# safebox.net
KiCad netlist of a schematic drawn in EAGLE
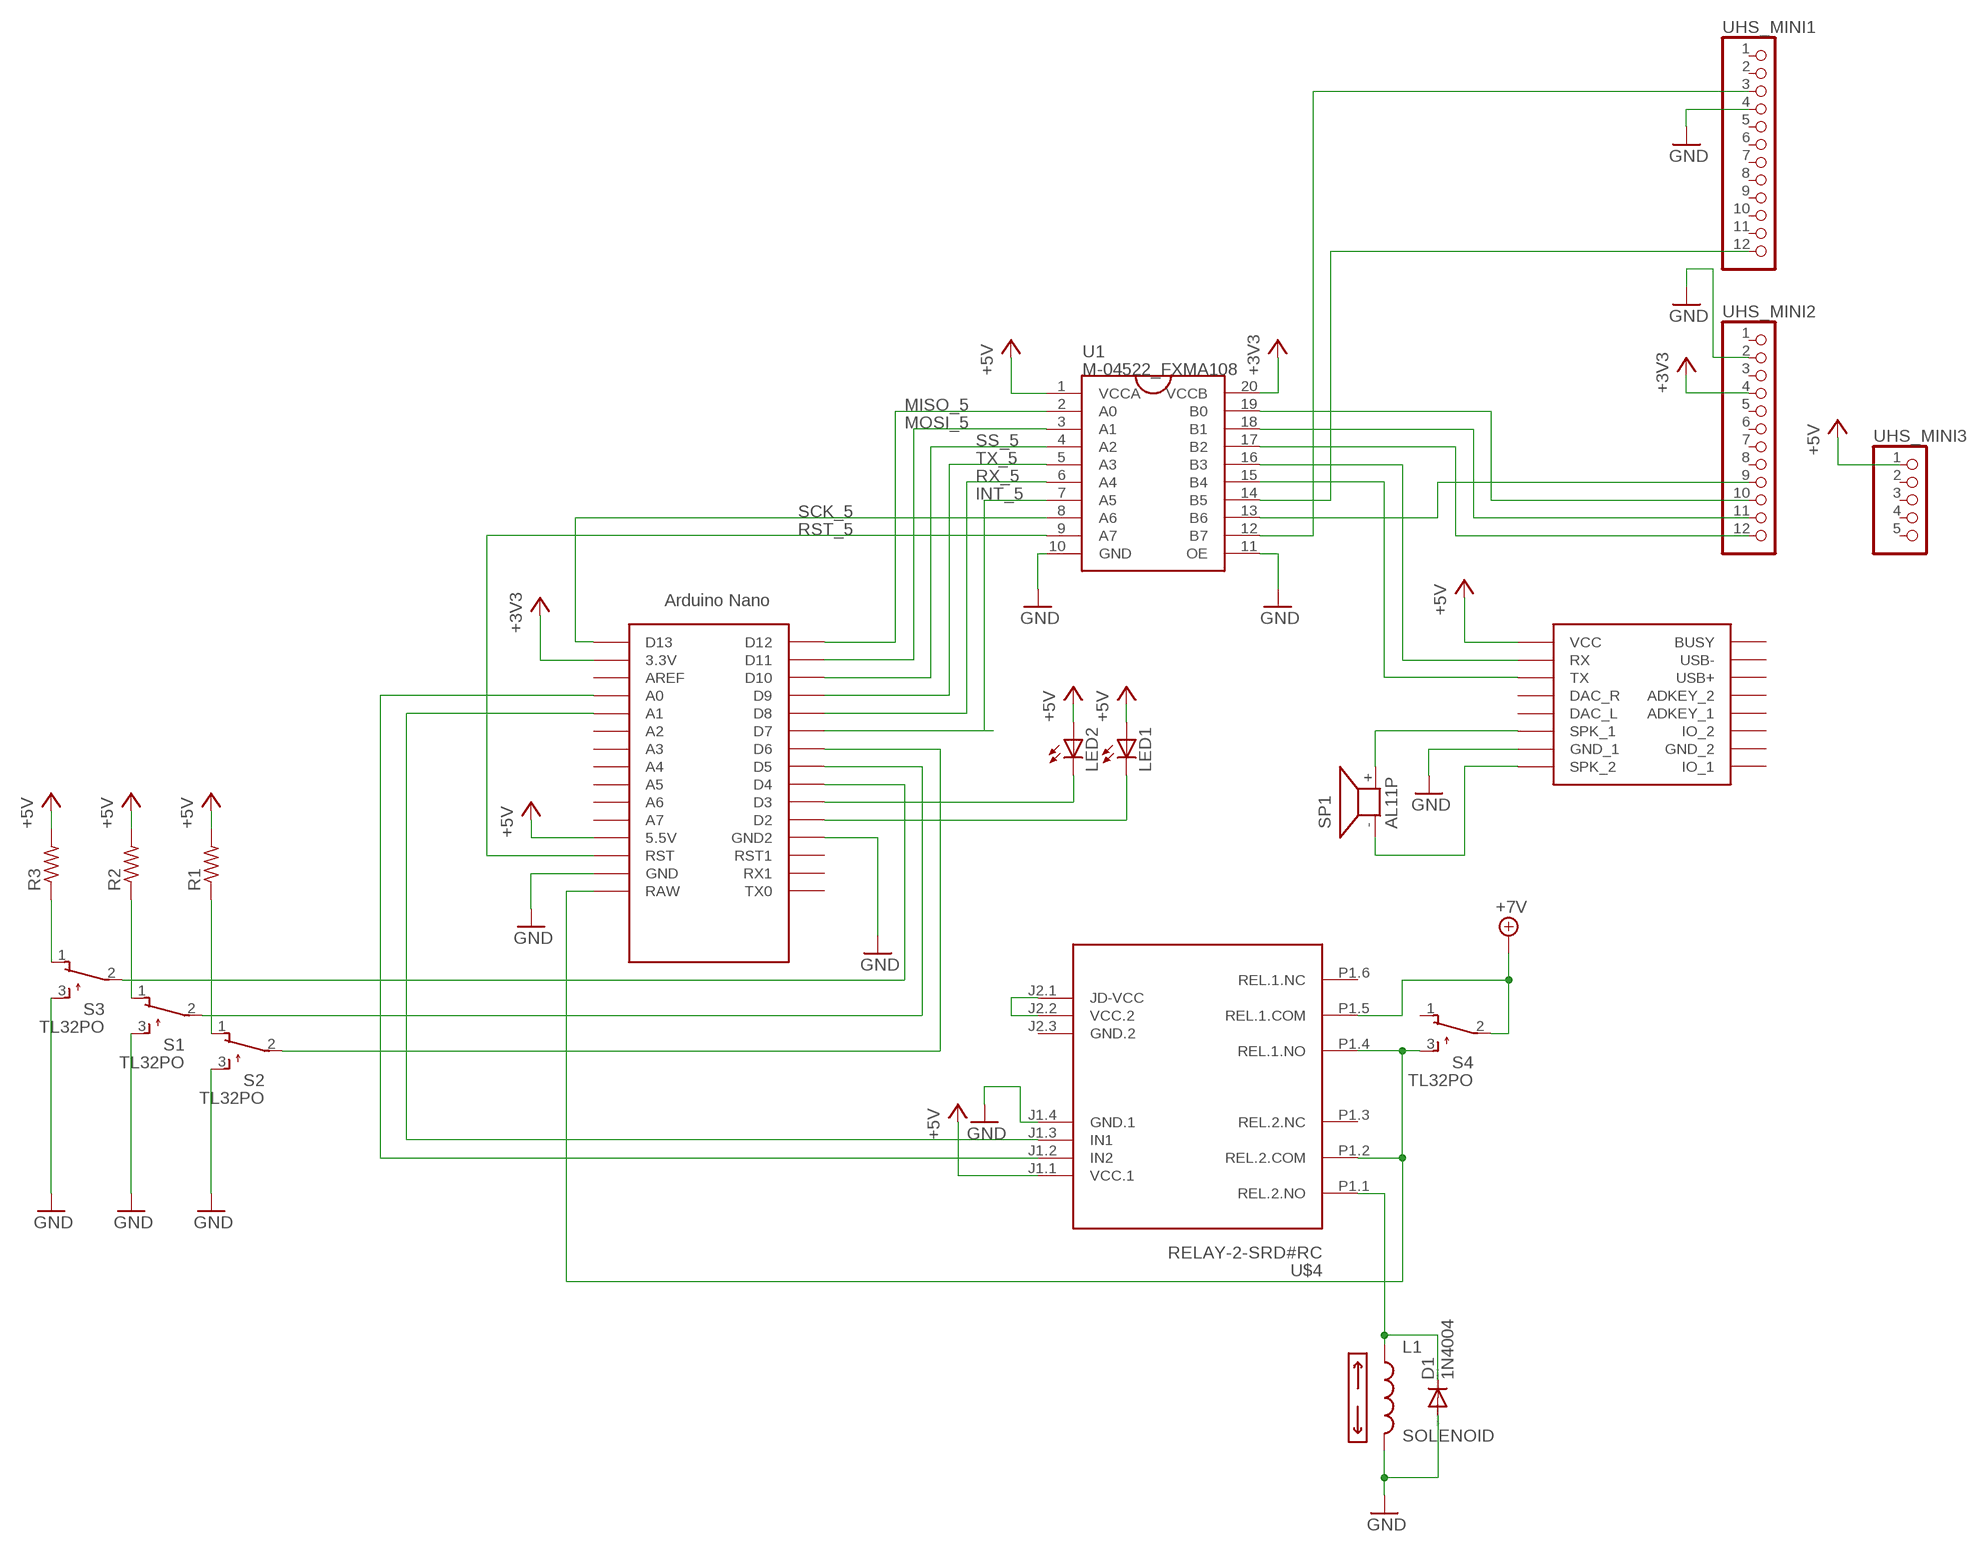
[diagram p0: schematic, sheet 1]

(export (version "E")
  (design (tool "Eeschema 10.0.6"))
  (components
    (comp (ref "D1")
      (value "1N4004")
      (footprint "eagle-import:DO41-10")
      (libsource (lib "eagle-import") (part "1N4004"))
    )
    (comp (ref "L1")
      (value "SOLENOID")
      (footprint "eagle-import:1X02")
      (libsource (lib "eagle-import") (part "SOLENOID"))
    )
    (comp (ref "LED1")
      (value "LED10MM")
      (footprint "eagle-import:LED10MM")
      (libsource (lib "eagle-import") (part "LED10MM"))
    )
    (comp (ref "LED2")
      (value "LED10MM")
      (footprint "eagle-import:LED10MM")
      (libsource (lib "eagle-import") (part "LED10MM"))
    )
    (comp (ref "R1")
      (value "R-US_0207/12")
      (footprint "eagle-import:0207_12")
      (libsource (lib "eagle-import") (part "R-US_0207/12"))
    )
    (comp (ref "R2")
      (value "R-US_0207/12")
      (footprint "eagle-import:0207_12")
      (libsource (lib "eagle-import") (part "R-US_0207/12"))
    )
    (comp (ref "R3")
      (value "R-US_0207/12")
      (footprint "eagle-import:0207_12")
      (libsource (lib "eagle-import") (part "R-US_0207/12"))
    )
    (comp (ref "S1")
      (value "TL32PO")
      (footprint "eagle-import:TL3XPO")
      (libsource (lib "eagle-import") (part "TL32PO"))
    )
    (comp (ref "S2")
      (value "TL32PO")
      (footprint "eagle-import:TL3XPO")
      (libsource (lib "eagle-import") (part "TL32PO"))
    )
    (comp (ref "S3")
      (value "TL32PO")
      (footprint "eagle-import:TL3XPO")
      (libsource (lib "eagle-import") (part "TL32PO"))
    )
    (comp (ref "S4")
      (value "TL32PO")
      (footprint "eagle-import:TL3XPO")
      (libsource (lib "eagle-import") (part "TL32PO"))
    )
    (comp (ref "SP1")
      (value "AL11P")
      (footprint "eagle-import:AL11P")
      (libsource (lib "eagle-import") (part "AL11P"))
    )
    (comp (ref "U$1")
      (value "NANO")
      (footprint "eagle-import:NANO")
      (libsource (lib "eagle-import") (part "NANO"))
    )
    (comp (ref "U$2")
      (value "DFPLAYER")
      (footprint "eagle-import:DFPLAYER")
      (libsource (lib "eagle-import") (part "DFPLAYER"))
    )
    (comp (ref "U$4")
      (value "RELAY-2-SRD#RC")
      (footprint "eagle-import:RELAY-2-SRD#RC")
      (libsource (lib "eagle-import") (part "RELAY-2-SRD#RC"))
    )
    (comp (ref "U1")
      (value "M-04522_FXMA108")
      (footprint "eagle-import:FXMA108")
      (libsource (lib "eagle-import") (part "M-04522_FXMA108"))
    )
    (comp (ref "UHS_MINI1")
      (value "PINHD-1X12")
      (footprint "eagle-import:1X12")
      (libsource (lib "eagle-import") (part "PINHD-1X12"))
    )
    (comp (ref "UHS_MINI2")
      (value "PINHD-1X12")
      (footprint "eagle-import:1X12")
      (libsource (lib "eagle-import") (part "PINHD-1X12"))
    )
    (comp (ref "UHS_MINI3")
      (value "PINHD-1X5")
      (footprint "eagle-import:1X05")
      (libsource (lib "eagle-import") (part "PINHD-1X5"))
    )
  )
  (nets
    (net (code "1") (name "+3V3") (class "Default")
      (node (ref "U$1") (pin "3.3V") (pinfunction "3.3V_3.3V") (pintype "bidirectional"))
      (node (ref "U1") (pin "20") (pinfunction "VCCB_20") (pintype "bidirectional"))
      (node (ref "UHS_MINI2") (pin "4") (pinfunction "4_4") (pintype "passive"))
    )
    (net (code "2") (name "+5V") (class "Default")
      (node (ref "LED1") (pin "A") (pinfunction "A_A") (pintype "passive"))
      (node (ref "LED2") (pin "A") (pinfunction "A_A") (pintype "passive"))
      (node (ref "R1") (pin "2") (pinfunction "2_2") (pintype "passive"))
      (node (ref "R2") (pin "2") (pinfunction "2_2") (pintype "passive"))
      (node (ref "R3") (pin "2") (pinfunction "2_2") (pintype "passive"))
      (node (ref "U$1") (pin "5V") (pinfunction "5.5V_5V") (pintype "bidirectional"))
      (node (ref "U$2") (pin "VCC") (pinfunction "VCC_VCC") (pintype "bidirectional"))
      (node (ref "U$4") (pin "J1.1") (pinfunction "VCC.1_J1.1") (pintype "power_in"))
      (node (ref "U1") (pin "1") (pinfunction "VCCA_1") (pintype "bidirectional"))
      (node (ref "UHS_MINI3") (pin "1") (pinfunction "1_1") (pintype "passive"))
    )
    (net (code "3") (name "+7V") (class "Default")
      (node (ref "S4") (pin "2") (pinfunction "P_2") (pintype "passive"))
      (node (ref "U$4") (pin "P1.5") (pinfunction "REL.1.COM_P1.5") (pintype "bidirectional"))
    )
    (net (code "4") (name "/GND.2") (class "Default")
      (node (ref "U$4") (pin "J2.3") (pinfunction "GND.2_J2.3") (pintype "power_in"))
    )
    (net (code "5") (name "/INT_5") (class "Default")
      (node (ref "U1") (pin "7") (pinfunction "A5_7") (pintype "bidirectional"))
    )
    (net (code "6") (name "/MISO_5") (class "Default")
      (node (ref "U$1") (pin "D12") (pinfunction "D12_D12") (pintype "bidirectional"))
      (node (ref "U1") (pin "2") (pinfunction "A0_2") (pintype "bidirectional"))
    )
    (net (code "7") (name "/MOSI_5") (class "Default")
      (node (ref "U$1") (pin "D11") (pinfunction "D11_D11") (pintype "bidirectional"))
      (node (ref "U1") (pin "3") (pinfunction "A1_3") (pintype "bidirectional"))
    )
    (net (code "8") (name "/RST_5") (class "Default")
      (node (ref "U$1") (pin "RST") (pinfunction "RST_RST") (pintype "bidirectional"))
      (node (ref "U1") (pin "9") (pinfunction "A7_9") (pintype "bidirectional"))
    )
    (net (code "9") (name "/RX_5") (class "Default")
      (node (ref "U$1") (pin "D8") (pinfunction "D8_D8") (pintype "bidirectional"))
      (node (ref "U1") (pin "6") (pinfunction "A4_6") (pintype "bidirectional"))
    )
    (net (code "10") (name "/SCK_5") (class "Default")
      (node (ref "U$1") (pin "D13") (pinfunction "D13_D13") (pintype "bidirectional"))
      (node (ref "U1") (pin "8") (pinfunction "A6_8") (pintype "bidirectional"))
    )
    (net (code "11") (name "/SS_5") (class "Default")
      (node (ref "U$1") (pin "D10") (pinfunction "D10_D10") (pintype "bidirectional"))
      (node (ref "U1") (pin "4") (pinfunction "A2_4") (pintype "bidirectional"))
    )
    (net (code "12") (name "/TX_5") (class "Default")
      (node (ref "U$1") (pin "D9") (pinfunction "D9_D9") (pintype "bidirectional"))
      (node (ref "U1") (pin "5") (pinfunction "A3_5") (pintype "bidirectional"))
    )
    (net (code "13") (name "GND") (class "Default")
      (node (ref "D1") (pin "A") (pinfunction "A_A") (pintype "passive"))
      (node (ref "L1") (pin "2") (pinfunction "2_2") (pintype "passive"))
      (node (ref "S1") (pin "3") (pinfunction "S_3") (pintype "passive"))
      (node (ref "S2") (pin "3") (pinfunction "S_3") (pintype "passive"))
      (node (ref "S3") (pin "3") (pinfunction "S_3") (pintype "passive"))
      (node (ref "U$1") (pin "GND") (pinfunction "GND_GND") (pintype "bidirectional"))
      (node (ref "U$1") (pin "GND1") (pinfunction "GND2_GND1") (pintype "bidirectional"))
      (node (ref "U$2") (pin "GND_1") (pinfunction "GND_1_GND_1") (pintype "bidirectional"))
      (node (ref "U$4") (pin "J1.4") (pinfunction "GND.1_J1.4") (pintype "power_in"))
      (node (ref "U1") (pin "10") (pinfunction "GND_10") (pintype "bidirectional"))
      (node (ref "U1") (pin "11") (pinfunction "OE_11") (pintype "bidirectional"))
      (node (ref "UHS_MINI1") (pin "4") (pinfunction "4_4") (pintype "passive"))
      (node (ref "UHS_MINI2") (pin "2") (pinfunction "2_2") (pintype "passive"))
    )
    (net (code "14") (name "Net-(LED1-C)") (class "Default")
      (node (ref "LED1") (pin "K") (pinfunction "C_K") (pintype "passive"))
      (node (ref "U$1") (pin "D2") (pinfunction "D2_D2") (pintype "bidirectional"))
    )
    (net (code "15") (name "Net-(LED2-C)") (class "Default")
      (node (ref "LED2") (pin "K") (pinfunction "C_K") (pintype "passive"))
      (node (ref "U$1") (pin "D3") (pinfunction "D3_D3") (pintype "bidirectional"))
    )
    (net (code "16") (name "Net-(S1-O)") (class "Default")
      (node (ref "R2") (pin "1") (pinfunction "1_1") (pintype "passive"))
      (node (ref "S1") (pin "1") (pinfunction "O_1") (pintype "passive"))
    )
    (net (code "17") (name "Net-(S1-P)") (class "Default")
      (node (ref "S1") (pin "2") (pinfunction "P_2") (pintype "passive"))
      (node (ref "U$1") (pin "D5") (pinfunction "D5_D5") (pintype "bidirectional"))
    )
    (net (code "18") (name "Net-(S2-O)") (class "Default")
      (node (ref "R1") (pin "1") (pinfunction "1_1") (pintype "passive"))
      (node (ref "S2") (pin "1") (pinfunction "O_1") (pintype "passive"))
    )
    (net (code "19") (name "Net-(S2-P)") (class "Default")
      (node (ref "S2") (pin "2") (pinfunction "P_2") (pintype "passive"))
      (node (ref "U$1") (pin "D6") (pinfunction "D6_D6") (pintype "bidirectional"))
    )
    (net (code "20") (name "Net-(S3-O)") (class "Default")
      (node (ref "R3") (pin "1") (pinfunction "1_1") (pintype "passive"))
      (node (ref "S3") (pin "1") (pinfunction "O_1") (pintype "passive"))
    )
    (net (code "21") (name "Net-(S3-P)") (class "Default")
      (node (ref "S3") (pin "2") (pinfunction "P_2") (pintype "passive"))
      (node (ref "U$1") (pin "D4") (pinfunction "D4_D4") (pintype "bidirectional"))
    )
    (net (code "22") (name "Net-(S4-S)") (class "Default")
      (node (ref "S4") (pin "3") (pinfunction "S_3") (pintype "passive"))
      (node (ref "U$1") (pin "RAW") (pinfunction "RAW_RAW") (pintype "bidirectional"))
      (node (ref "U$4") (pin "P1.2") (pinfunction "REL.2.COM_P1.2") (pintype "bidirectional"))
      (node (ref "U$4") (pin "P1.4") (pinfunction "REL.1.NO_P1.4") (pintype "bidirectional"))
    )
    (net (code "23") (name "Net-(SP1-1)") (class "Default")
      (node (ref "SP1") (pin "-") (pinfunction "1_-") (pintype "passive"))
      (node (ref "U$2") (pin "SPK2") (pinfunction "SPK_2_SPK2") (pintype "bidirectional"))
    )
    (net (code "24") (name "Net-(SP1-2)") (class "Default")
      (node (ref "SP1") (pin "+") (pinfunction "2_+") (pintype "passive"))
      (node (ref "U$2") (pin "SPK1") (pinfunction "SPK_1_SPK1") (pintype "bidirectional"))
    )
    (net (code "25") (name "Net-(U$4-IN1)") (class "Default")
      (node (ref "U$1") (pin "A1") (pinfunction "A1_A1") (pintype "bidirectional"))
      (node (ref "U$4") (pin "J1.3") (pinfunction "IN1_J1.3") (pintype "bidirectional"))
    )
    (net (code "26") (name "Net-(U$4-IN2)") (class "Default")
      (node (ref "U$1") (pin "A0") (pinfunction "A0_A0") (pintype "bidirectional"))
      (node (ref "U$4") (pin "J1.2") (pinfunction "IN2_J1.2") (pintype "bidirectional"))
    )
    (net (code "27") (name "Net-(U$4-JD-VCC)") (class "Default")
      (node (ref "U$4") (pin "J2.1") (pinfunction "JD-VCC_J2.1") (pintype "bidirectional"))
      (node (ref "U$4") (pin "J2.2") (pinfunction "VCC.2_J2.2") (pintype "power_in"))
    )
    (net (code "28") (name "Net-(U$4-REL.2.NO)") (class "Default")
      (node (ref "D1") (pin "C") (pinfunction "C_C") (pintype "passive"))
      (node (ref "L1") (pin "1") (pinfunction "1_1") (pintype "passive"))
      (node (ref "U$4") (pin "P1.1") (pinfunction "REL.2.NO_P1.1") (pintype "bidirectional"))
    )
    (net (code "29") (name "Net-(U1-B0)") (class "Default")
      (node (ref "U1") (pin "19") (pinfunction "B0_19") (pintype "bidirectional"))
      (node (ref "UHS_MINI2") (pin "10") (pinfunction "10_10") (pintype "passive"))
    )
    (net (code "30") (name "Net-(U1-B1)") (class "Default")
      (node (ref "U1") (pin "18") (pinfunction "B1_18") (pintype "bidirectional"))
      (node (ref "UHS_MINI2") (pin "11") (pinfunction "11_11") (pintype "passive"))
    )
    (net (code "31") (name "Net-(U1-B2)") (class "Default")
      (node (ref "U1") (pin "17") (pinfunction "B2_17") (pintype "bidirectional"))
      (node (ref "UHS_MINI2") (pin "12") (pinfunction "12_12") (pintype "passive"))
    )
    (net (code "32") (name "Net-(U1-B3)") (class "Default")
      (node (ref "U$2") (pin "RX") (pinfunction "RX_RX") (pintype "bidirectional"))
      (node (ref "U1") (pin "16") (pinfunction "B3_16") (pintype "bidirectional"))
    )
    (net (code "33") (name "Net-(U1-B4)") (class "Default")
      (node (ref "U$2") (pin "TX") (pinfunction "TX_TX") (pintype "bidirectional"))
      (node (ref "U1") (pin "15") (pinfunction "B4_15") (pintype "bidirectional"))
    )
    (net (code "34") (name "Net-(U1-B5)") (class "Default")
      (node (ref "U1") (pin "14") (pinfunction "B5_14") (pintype "bidirectional"))
      (node (ref "UHS_MINI1") (pin "12") (pinfunction "12_12") (pintype "passive"))
    )
    (net (code "35") (name "Net-(U1-B6)") (class "Default")
      (node (ref "U1") (pin "13") (pinfunction "B6_13") (pintype "bidirectional"))
      (node (ref "UHS_MINI2") (pin "9") (pinfunction "9_9") (pintype "passive"))
    )
    (net (code "36") (name "Net-(U1-B7)") (class "Default")
      (node (ref "U1") (pin "12") (pinfunction "B7_12") (pintype "bidirectional"))
      (node (ref "UHS_MINI1") (pin "3") (pinfunction "3_3") (pintype "passive"))
    )
    (net (code "37") (name "unconnected-(S4-O-Pad1)") (class "Default")
      (node (ref "S4") (pin "1") (pinfunction "O_1") (pintype "passive"))
    )
    (net (code "38") (name "unconnected-(U$1-PadA2)") (class "Default")
      (node (ref "U$1") (pin "A2") (pinfunction "A2_A2") (pintype "bidirectional"))
    )
    (net (code "39") (name "unconnected-(U$1-PadA3)") (class "Default")
      (node (ref "U$1") (pin "A3") (pinfunction "A3_A3") (pintype "bidirectional"))
    )
    (net (code "40") (name "unconnected-(U$1-PadA4)") (class "Default")
      (node (ref "U$1") (pin "A4") (pinfunction "A4_A4") (pintype "bidirectional"))
    )
    (net (code "41") (name "unconnected-(U$1-PadA5)") (class "Default")
      (node (ref "U$1") (pin "A5") (pinfunction "A5_A5") (pintype "bidirectional"))
    )
    (net (code "42") (name "unconnected-(U$1-PadA6)") (class "Default")
      (node (ref "U$1") (pin "A6") (pinfunction "A6_A6") (pintype "bidirectional"))
    )
    (net (code "43") (name "unconnected-(U$1-PadA7)") (class "Default")
      (node (ref "U$1") (pin "A7") (pinfunction "A7_A7") (pintype "bidirectional"))
    )
    (net (code "44") (name "unconnected-(U$1-PadAREF)") (class "Default")
      (node (ref "U$1") (pin "AREF") (pinfunction "AREF_AREF") (pintype "bidirectional"))
    )
    (net (code "45") (name "unconnected-(U$1-PadD7)") (class "Default")
      (node (ref "U$1") (pin "D7") (pinfunction "D7_D7") (pintype "bidirectional"))
    )
    (net (code "46") (name "unconnected-(U$1-PadICSP1)") (class "Default")
      (node (ref "U$1") (pin "ICSP1") (pinfunction "ICSP1_ICSP1") (pintype "bidirectional"))
    )
    (net (code "47") (name "unconnected-(U$1-PadICSP2)") (class "Default")
      (node (ref "U$1") (pin "ICSP2") (pinfunction "ICSP2_ICSP2") (pintype "bidirectional"))
    )
    (net (code "48") (name "unconnected-(U$1-PadICSP3)") (class "Default")
      (node (ref "U$1") (pin "ICSP3") (pinfunction "ICSP3_ICSP3") (pintype "bidirectional"))
    )
    (net (code "49") (name "unconnected-(U$1-PadICSP4)") (class "Default")
      (node (ref "U$1") (pin "ICSP4") (pinfunction "ICSP4_ICSP4") (pintype "bidirectional"))
    )
    (net (code "50") (name "unconnected-(U$1-PadICSP5)") (class "Default")
      (node (ref "U$1") (pin "ICSP5") (pinfunction "ICSP5_ICSP5") (pintype "bidirectional"))
    )
    (net (code "51") (name "unconnected-(U$1-PadICSP6)") (class "Default")
      (node (ref "U$1") (pin "ICSP6") (pinfunction "ICSP6_ICSP6") (pintype "bidirectional"))
    )
    (net (code "52") (name "unconnected-(U$1-PadRST1)") (class "Default")
      (node (ref "U$1") (pin "RST1") (pinfunction "RST1_RST1") (pintype "bidirectional"))
    )
    (net (code "53") (name "unconnected-(U$1-PadRX1)") (class "Default")
      (node (ref "U$1") (pin "RX1") (pinfunction "RX1_RX1") (pintype "bidirectional"))
    )
    (net (code "54") (name "unconnected-(U$1-PadTX0)") (class "Default")
      (node (ref "U$1") (pin "TX0") (pinfunction "TX0_TX0") (pintype "bidirectional"))
    )
    (net (code "55") (name "unconnected-(U$2-ADKEY_1-PadADKEY1)") (class "Default")
      (node (ref "U$2") (pin "ADKEY1") (pinfunction "ADKEY_1_ADKEY1") (pintype "bidirectional"))
    )
    (net (code "56") (name "unconnected-(U$2-ADKEY_2-PadADKEY2)") (class "Default")
      (node (ref "U$2") (pin "ADKEY2") (pinfunction "ADKEY_2_ADKEY2") (pintype "bidirectional"))
    )
    (net (code "57") (name "unconnected-(U$2-IO_1-PadIO1)") (class "Default")
      (node (ref "U$2") (pin "IO1") (pinfunction "IO_1_IO1") (pintype "bidirectional"))
    )
    (net (code "58") (name "unconnected-(U$2-IO_2-PadIO2)") (class "Default")
      (node (ref "U$2") (pin "IO2") (pinfunction "IO_2_IO2") (pintype "bidirectional"))
    )
    (net (code "59") (name "unconnected-(U$2-PadBUSY)") (class "Default")
      (node (ref "U$2") (pin "BUSY") (pinfunction "BUSY_BUSY") (pintype "bidirectional"))
    )
    (net (code "60") (name "unconnected-(U$2-PadDAC_L)") (class "Default")
      (node (ref "U$2") (pin "DAC_L") (pinfunction "DAC_L_DAC_L") (pintype "bidirectional"))
    )
    (net (code "61") (name "unconnected-(U$2-PadDAC_R)") (class "Default")
      (node (ref "U$2") (pin "DAC_R") (pinfunction "DAC_R_DAC_R") (pintype "bidirectional"))
    )
    (net (code "62") (name "unconnected-(U$2-PadGND_2)") (class "Default")
      (node (ref "U$2") (pin "GND_2") (pinfunction "GND_2_GND_2") (pintype "bidirectional"))
    )
    (net (code "63") (name "unconnected-(U$2-PadUSB+)") (class "Default")
      (node (ref "U$2") (pin "USB+") (pinfunction "USB+_USB+") (pintype "bidirectional"))
    )
    (net (code "64") (name "unconnected-(U$2-PadUSB-)") (class "Default")
      (node (ref "U$2") (pin "USB-") (pinfunction "USB-_USB-") (pintype "bidirectional"))
    )
    (net (code "65") (name "unconnected-(U$4-REL.1.NC-PadP1.6)") (class "Default")
      (node (ref "U$4") (pin "P1.6") (pinfunction "REL.1.NC_P1.6") (pintype "bidirectional"))
    )
    (net (code "66") (name "unconnected-(U$4-REL.2.NC-PadP1.3)") (class "Default")
      (node (ref "U$4") (pin "P1.3") (pinfunction "REL.2.NC_P1.3") (pintype "bidirectional"))
    )
    (net (code "67") (name "unconnected-(UHS_MINI1-Pad1)") (class "Default")
      (node (ref "UHS_MINI1") (pin "1") (pinfunction "1_1") (pintype "passive"))
    )
    (net (code "68") (name "unconnected-(UHS_MINI1-Pad2)") (class "Default")
      (node (ref "UHS_MINI1") (pin "2") (pinfunction "2_2") (pintype "passive"))
    )
    (net (code "69") (name "unconnected-(UHS_MINI1-Pad5)") (class "Default")
      (node (ref "UHS_MINI1") (pin "5") (pinfunction "5_5") (pintype "passive"))
    )
    (net (code "70") (name "unconnected-(UHS_MINI1-Pad6)") (class "Default")
      (node (ref "UHS_MINI1") (pin "6") (pinfunction "6_6") (pintype "passive"))
    )
    (net (code "71") (name "unconnected-(UHS_MINI1-Pad7)") (class "Default")
      (node (ref "UHS_MINI1") (pin "7") (pinfunction "7_7") (pintype "passive"))
    )
    (net (code "72") (name "unconnected-(UHS_MINI1-Pad8)") (class "Default")
      (node (ref "UHS_MINI1") (pin "8") (pinfunction "8_8") (pintype "passive"))
    )
    (net (code "73") (name "unconnected-(UHS_MINI1-Pad9)") (class "Default")
      (node (ref "UHS_MINI1") (pin "9") (pinfunction "9_9") (pintype "passive"))
    )
    (net (code "74") (name "unconnected-(UHS_MINI1-Pad10)") (class "Default")
      (node (ref "UHS_MINI1") (pin "10") (pinfunction "10_10") (pintype "passive"))
    )
    (net (code "75") (name "unconnected-(UHS_MINI1-Pad11)") (class "Default")
      (node (ref "UHS_MINI1") (pin "11") (pinfunction "11_11") (pintype "passive"))
    )
    (net (code "76") (name "unconnected-(UHS_MINI2-Pad1)") (class "Default")
      (node (ref "UHS_MINI2") (pin "1") (pinfunction "1_1") (pintype "passive"))
    )
    (net (code "77") (name "unconnected-(UHS_MINI2-Pad3)") (class "Default")
      (node (ref "UHS_MINI2") (pin "3") (pinfunction "3_3") (pintype "passive"))
    )
    (net (code "78") (name "unconnected-(UHS_MINI2-Pad5)") (class "Default")
      (node (ref "UHS_MINI2") (pin "5") (pinfunction "5_5") (pintype "passive"))
    )
    (net (code "79") (name "unconnected-(UHS_MINI2-Pad6)") (class "Default")
      (node (ref "UHS_MINI2") (pin "6") (pinfunction "6_6") (pintype "passive"))
    )
    (net (code "80") (name "unconnected-(UHS_MINI2-Pad7)") (class "Default")
      (node (ref "UHS_MINI2") (pin "7") (pinfunction "7_7") (pintype "passive"))
    )
    (net (code "81") (name "unconnected-(UHS_MINI2-Pad8)") (class "Default")
      (node (ref "UHS_MINI2") (pin "8") (pinfunction "8_8") (pintype "passive"))
    )
    (net (code "82") (name "unconnected-(UHS_MINI3-Pad2)") (class "Default")
      (node (ref "UHS_MINI3") (pin "2") (pinfunction "2_2") (pintype "passive"))
    )
    (net (code "83") (name "unconnected-(UHS_MINI3-Pad3)") (class "Default")
      (node (ref "UHS_MINI3") (pin "3") (pinfunction "3_3") (pintype "passive"))
    )
    (net (code "84") (name "unconnected-(UHS_MINI3-Pad4)") (class "Default")
      (node (ref "UHS_MINI3") (pin "4") (pinfunction "4_4") (pintype "passive"))
    )
    (net (code "85") (name "unconnected-(UHS_MINI3-Pad5)") (class "Default")
      (node (ref "UHS_MINI3") (pin "5") (pinfunction "5_5") (pintype "passive"))
    )
  )
)
